# MEMS-preamp_v04.net
KiCad netlist of a schematic drawn in EAGLE
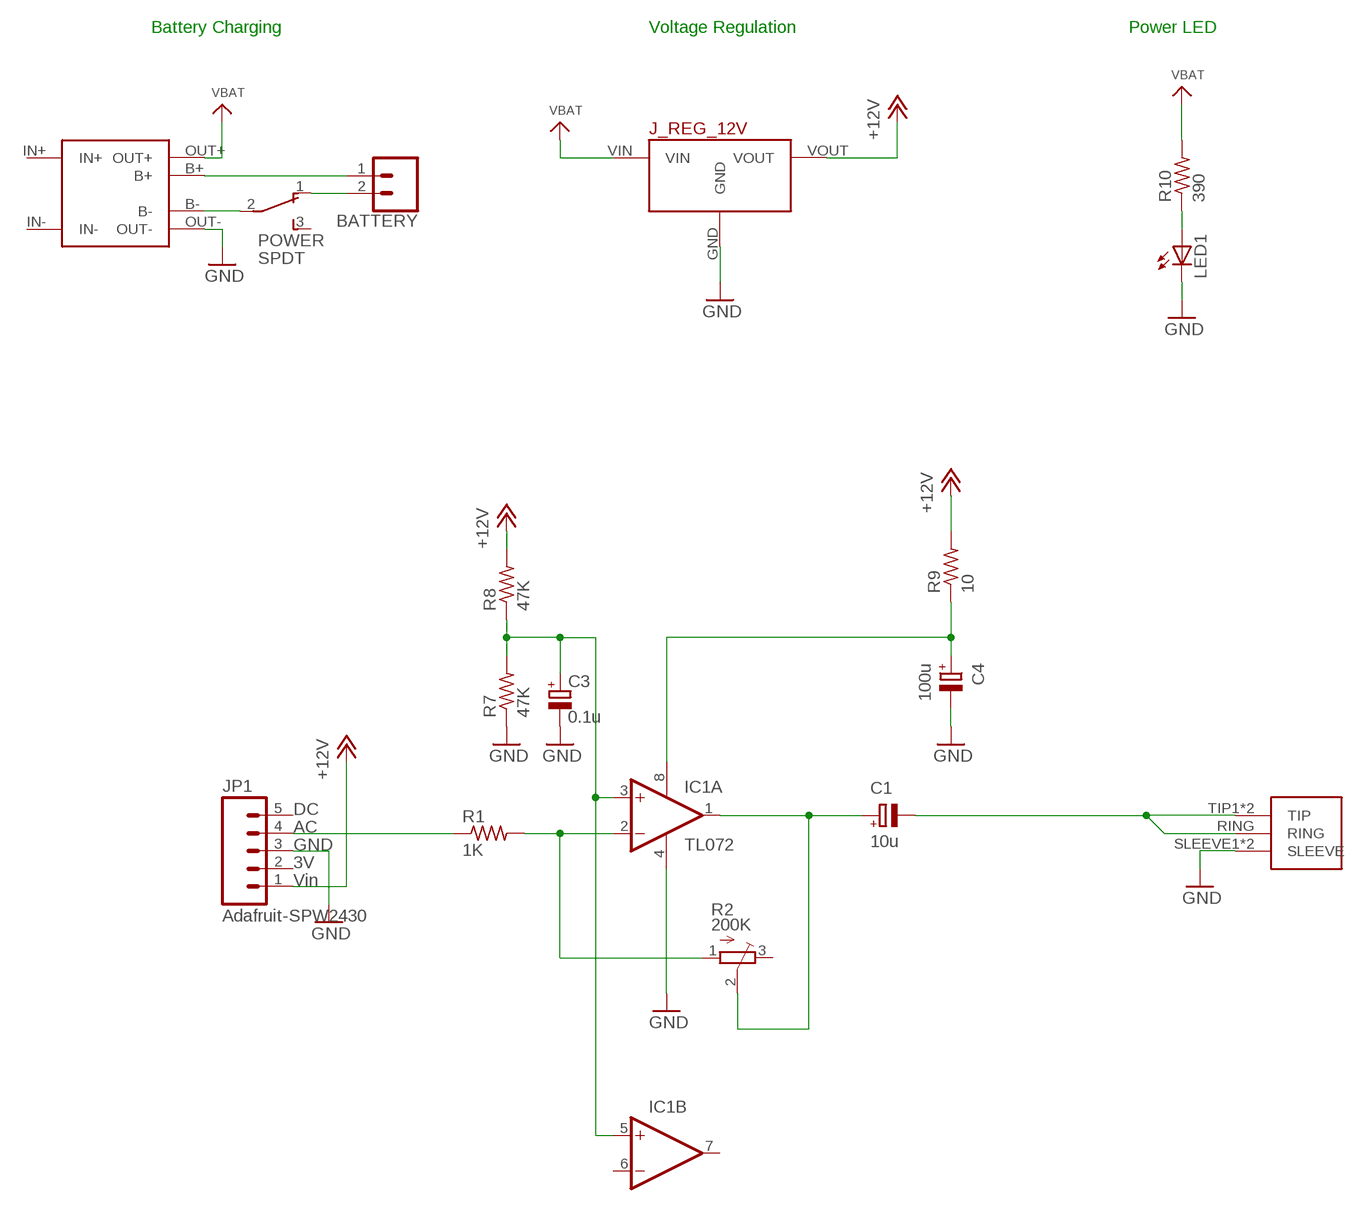
[diagram p0: schematic, sheet 1]

(export (version "E")
  (design (tool "Eeschema 10.0.6"))
  (components
    (comp (ref "BATTERY")
      (value "CONN_02LOCK")
      (footprint "eagle-import:1X02_LOCK")
      (libsource (lib "eagle-import") (part "CONN_02LOCK"))
    )
    (comp (ref "C1")
      (value "10u")
      (footprint "eagle-import:E2,5-5")
      (libsource (lib "eagle-import") (part "CPOL-EUE2.5-5"))
    )
    (comp (ref "C3")
      (value "0.1u")
      (footprint "eagle-import:E2,5-5")
      (libsource (lib "eagle-import") (part "CPOL-EUE2.5-5"))
    )
    (comp (ref "C4")
      (value "100u")
      (footprint "eagle-import:E2,5-5")
      (libsource (lib "eagle-import") (part "CPOL-EUE2.5-5"))
    )
    (comp (ref "IC1")
      (value "OPA2134PA")
      (footprint "eagle-import:DIL08")
      (fields (field (name "IC_NAME") "TL072"))
      (libsource (lib "eagle-import") (part "OPA2PA134"))
    )
    (comp (ref "JP1")
      (value "Adafruit-SPW2430")
      (footprint "eagle-import:1X05_LOCK")
      (fields
        (field (name "CON1") "Vin")
        (field (name "CON2") "3V")
        (field (name "CON3") "GND")
        (field (name "CON4") "AC")
        (field (name "CON5") "DC")
      )
      (libsource (lib "eagle-import") (part "M05LOCK"))
    )
    (comp (ref "J_REG_12V")
      (value "POLOLU_VOLTAGE_REGULATORS_3PIN")
      (footprint "eagle-import:POLOLU_5V-12V_STEPUP_U3V12F5-U3V12F12")
      (libsource (lib "eagle-import") (part "POLOLU_VOLTAGE_REGULATORS_3PIN"))
    )
    (comp (ref "LED1")
      (value "LED3MM")
      (footprint "eagle-import:LED3MM")
      (libsource (lib "eagle-import") (part "LED3MM"))
    )
    (comp (ref "POWER")
      (value "SPDT")
      (footprint "eagle-import:SWITCH_SPDT-TE-CONNECT")
      (libsource (lib "eagle-import") (part "SWITCH_SPDTTE-CONNECT"))
    )
    (comp (ref "R1")
      (value "1K")
      (footprint "eagle-import:0204_5")
      (libsource (lib "eagle-import") (part "R-US_0204/5"))
    )
    (comp (ref "R2")
      (value "200K")
      (footprint "eagle-import:TRIM-3386")
      (libsource (lib "eagle-import") (part "TRIMPOT3386"))
    )
    (comp (ref "R7")
      (value "47K")
      (footprint "eagle-import:0204_5")
      (libsource (lib "eagle-import") (part "R-US_0204/5"))
    )
    (comp (ref "R8")
      (value "47K")
      (footprint "eagle-import:0204_5")
      (libsource (lib "eagle-import") (part "R-US_0204/5"))
    )
    (comp (ref "R9")
      (value "10")
      (footprint "eagle-import:0204_5")
      (libsource (lib "eagle-import") (part "R-US_0204/5"))
    )
    (comp (ref "R10")
      (value "390")
      (footprint "eagle-import:0204_5")
      (libsource (lib "eagle-import") (part "R-US_0204/5"))
    )
    (comp (ref "U$1")
      (value "1/8\"-F-STEREO-PCB")
      (footprint "eagle-import:1_8_-F-STEREO-PCB")
      (libsource (lib "eagle-import") (part "1/8{dblquote}-F-STEREO-PCB"))
    )
    (comp (ref "USB-LIPO-CHARGER")
      (value "TP4056-MODULE")
      (footprint "eagle-import:TP4056-LITHIUM-PROTECTED-MODULE")
      (libsource (lib "eagle-import") (part "TP4056-MODULE"))
    )
  )
  (nets
    (net (code "1") (name "+12V") (class "Default")
      (node (ref "JP1") (pin "1") (pinfunction "1_1") (pintype "passive"))
      (node (ref "J_REG_12V") (pin "VOUT") (pinfunction "VOUT_VOUT") (pintype "bidirectional"))
      (node (ref "R8") (pin "2") (pinfunction "2_2") (pintype "passive"))
      (node (ref "R9") (pin "2") (pinfunction "2_2") (pintype "passive"))
    )
    (net (code "2") (name "/IN+") (class "Default")
      (node (ref "USB-LIPO-CHARGER") (pin "IN+") (pinfunction "IN+_IN+") (pintype "power_in"))
    )
    (net (code "3") (name "/IN-") (class "Default")
      (node (ref "USB-LIPO-CHARGER") (pin "IN-") (pinfunction "IN-_IN-") (pintype "power_in"))
    )
    (net (code "4") (name "GND") (class "Default")
      (node (ref "C3") (pin "-") (pinfunction "-_-") (pintype "passive"))
      (node (ref "C4") (pin "-") (pinfunction "-_-") (pintype "passive"))
      (node (ref "IC1") (pin "4") (pinfunction "V-_4") (pintype "power_in"))
      (node (ref "JP1") (pin "3") (pinfunction "3_3") (pintype "passive"))
      (node (ref "J_REG_12V") (pin "GND") (pinfunction "GND_GND") (pintype "bidirectional"))
      (node (ref "LED1") (pin "K") (pinfunction "C_K") (pintype "passive"))
      (node (ref "R7") (pin "1") (pinfunction "1_1") (pintype "passive"))
      (node (ref "U$1") (pin "SLEEVE1") (pinfunction "SLEEVE_SLEEVE1") (pintype "bidirectional"))
      (node (ref "U$1") (pin "SLEEVE2") (pinfunction "SLEEVE_SLEEVE2") (pintype "bidirectional"))
      (node (ref "USB-LIPO-CHARGER") (pin "OUT-") (pinfunction "OUT-_OUT-") (pintype "power_in"))
    )
    (net (code "5") (name "Net-(BATTERY-Pad1)") (class "Default")
      (node (ref "BATTERY") (pin "1") (pinfunction "1_1") (pintype "passive"))
      (node (ref "USB-LIPO-CHARGER") (pin "B+") (pinfunction "B+_B+") (pintype "power_in"))
    )
    (net (code "6") (name "Net-(BATTERY-Pad2)") (class "Default")
      (node (ref "BATTERY") (pin "2") (pinfunction "2_2") (pintype "passive"))
      (node (ref "POWER") (pin "1") (pinfunction "1_1") (pintype "passive"))
    )
    (net (code "7") (name "Net-(C1-Pad-)") (class "Default")
      (node (ref "C1") (pin "-") (pinfunction "-_-") (pintype "passive"))
      (node (ref "U$1") (pin "RING") (pinfunction "RING_RING") (pintype "bidirectional"))
      (node (ref "U$1") (pin "TIP1") (pinfunction "TIP_TIP1") (pintype "bidirectional"))
      (node (ref "U$1") (pin "TIP2") (pinfunction "TIP_TIP2") (pintype "bidirectional"))
    )
    (net (code "8") (name "Net-(IC1A-+IN)") (class "Default")
      (node (ref "C3") (pin "+") (pinfunction "+_+") (pintype "passive"))
      (node (ref "IC1") (pin "3") (pinfunction "+IN_3") (pintype "input"))
      (node (ref "IC1") (pin "5") (pinfunction "+IN_5") (pintype "input"))
      (node (ref "R7") (pin "2") (pinfunction "2_2") (pintype "passive"))
      (node (ref "R8") (pin "1") (pinfunction "1_1") (pintype "passive"))
    )
    (net (code "9") (name "Net-(IC1A--IN)") (class "Default")
      (node (ref "IC1") (pin "2") (pinfunction "-IN_2") (pintype "input"))
      (node (ref "R1") (pin "2") (pinfunction "2_2") (pintype "passive"))
      (node (ref "R2") (pin "1") (pinfunction "A_1") (pintype "passive"))
    )
    (net (code "10") (name "Net-(IC1A-OUT)") (class "Default")
      (node (ref "C1") (pin "+") (pinfunction "+_+") (pintype "passive"))
      (node (ref "IC1") (pin "1") (pinfunction "OUT_1") (pintype "output"))
      (node (ref "R2") (pin "2") (pinfunction "S_2") (pintype "passive"))
    )
    (net (code "11") (name "Net-(IC1A-V+)") (class "Default")
      (node (ref "C4") (pin "+") (pinfunction "+_+") (pintype "passive"))
      (node (ref "IC1") (pin "8") (pinfunction "V+_8") (pintype "power_in"))
      (node (ref "R9") (pin "1") (pinfunction "1_1") (pintype "passive"))
    )
    (net (code "12") (name "Net-(JP1-Pad4)") (class "Default")
      (node (ref "JP1") (pin "4") (pinfunction "4_4") (pintype "passive"))
      (node (ref "R1") (pin "1") (pinfunction "1_1") (pintype "passive"))
    )
    (net (code "13") (name "Net-(LED1-PadA)") (class "Default")
      (node (ref "LED1") (pin "A") (pinfunction "A_A") (pintype "passive"))
      (node (ref "R10") (pin "1") (pinfunction "1_1") (pintype "passive"))
    )
    (net (code "14") (name "Net-(POWER-Pad2)") (class "Default")
      (node (ref "POWER") (pin "2") (pinfunction "2_2") (pintype "passive"))
      (node (ref "USB-LIPO-CHARGER") (pin "B-") (pinfunction "B-_B-") (pintype "power_in"))
    )
    (net (code "15") (name "VBAT") (class "Default")
      (node (ref "J_REG_12V") (pin "VIN") (pinfunction "VIN_VIN") (pintype "bidirectional"))
      (node (ref "R10") (pin "2") (pinfunction "2_2") (pintype "passive"))
      (node (ref "USB-LIPO-CHARGER") (pin "OUT+") (pinfunction "OUT+_OUT+") (pintype "power_in"))
    )
    (net (code "16") (name "unconnected-(IC1B--IN-Pad6)") (class "Default")
      (node (ref "IC1") (pin "6") (pinfunction "-IN_6") (pintype "input"))
    )
    (net (code "17") (name "unconnected-(IC1B-OUT-Pad7)") (class "Default")
      (node (ref "IC1") (pin "7") (pinfunction "OUT_7") (pintype "output"))
    )
    (net (code "18") (name "unconnected-(JP1-Pad2)") (class "Default")
      (node (ref "JP1") (pin "2") (pinfunction "2_2") (pintype "passive"))
    )
    (net (code "19") (name "unconnected-(JP1-Pad5)") (class "Default")
      (node (ref "JP1") (pin "5") (pinfunction "5_5") (pintype "passive"))
    )
    (net (code "20") (name "unconnected-(POWER-Pad3)") (class "Default")
      (node (ref "POWER") (pin "3") (pinfunction "3_3") (pintype "passive"))
    )
    (net (code "21") (name "unconnected-(R2-E-Pad3)") (class "Default")
      (node (ref "R2") (pin "3") (pinfunction "E_3") (pintype "passive"))
    )
  )
)
